# design.net
KiCad netlist of a schematic drawn in EasyEDA
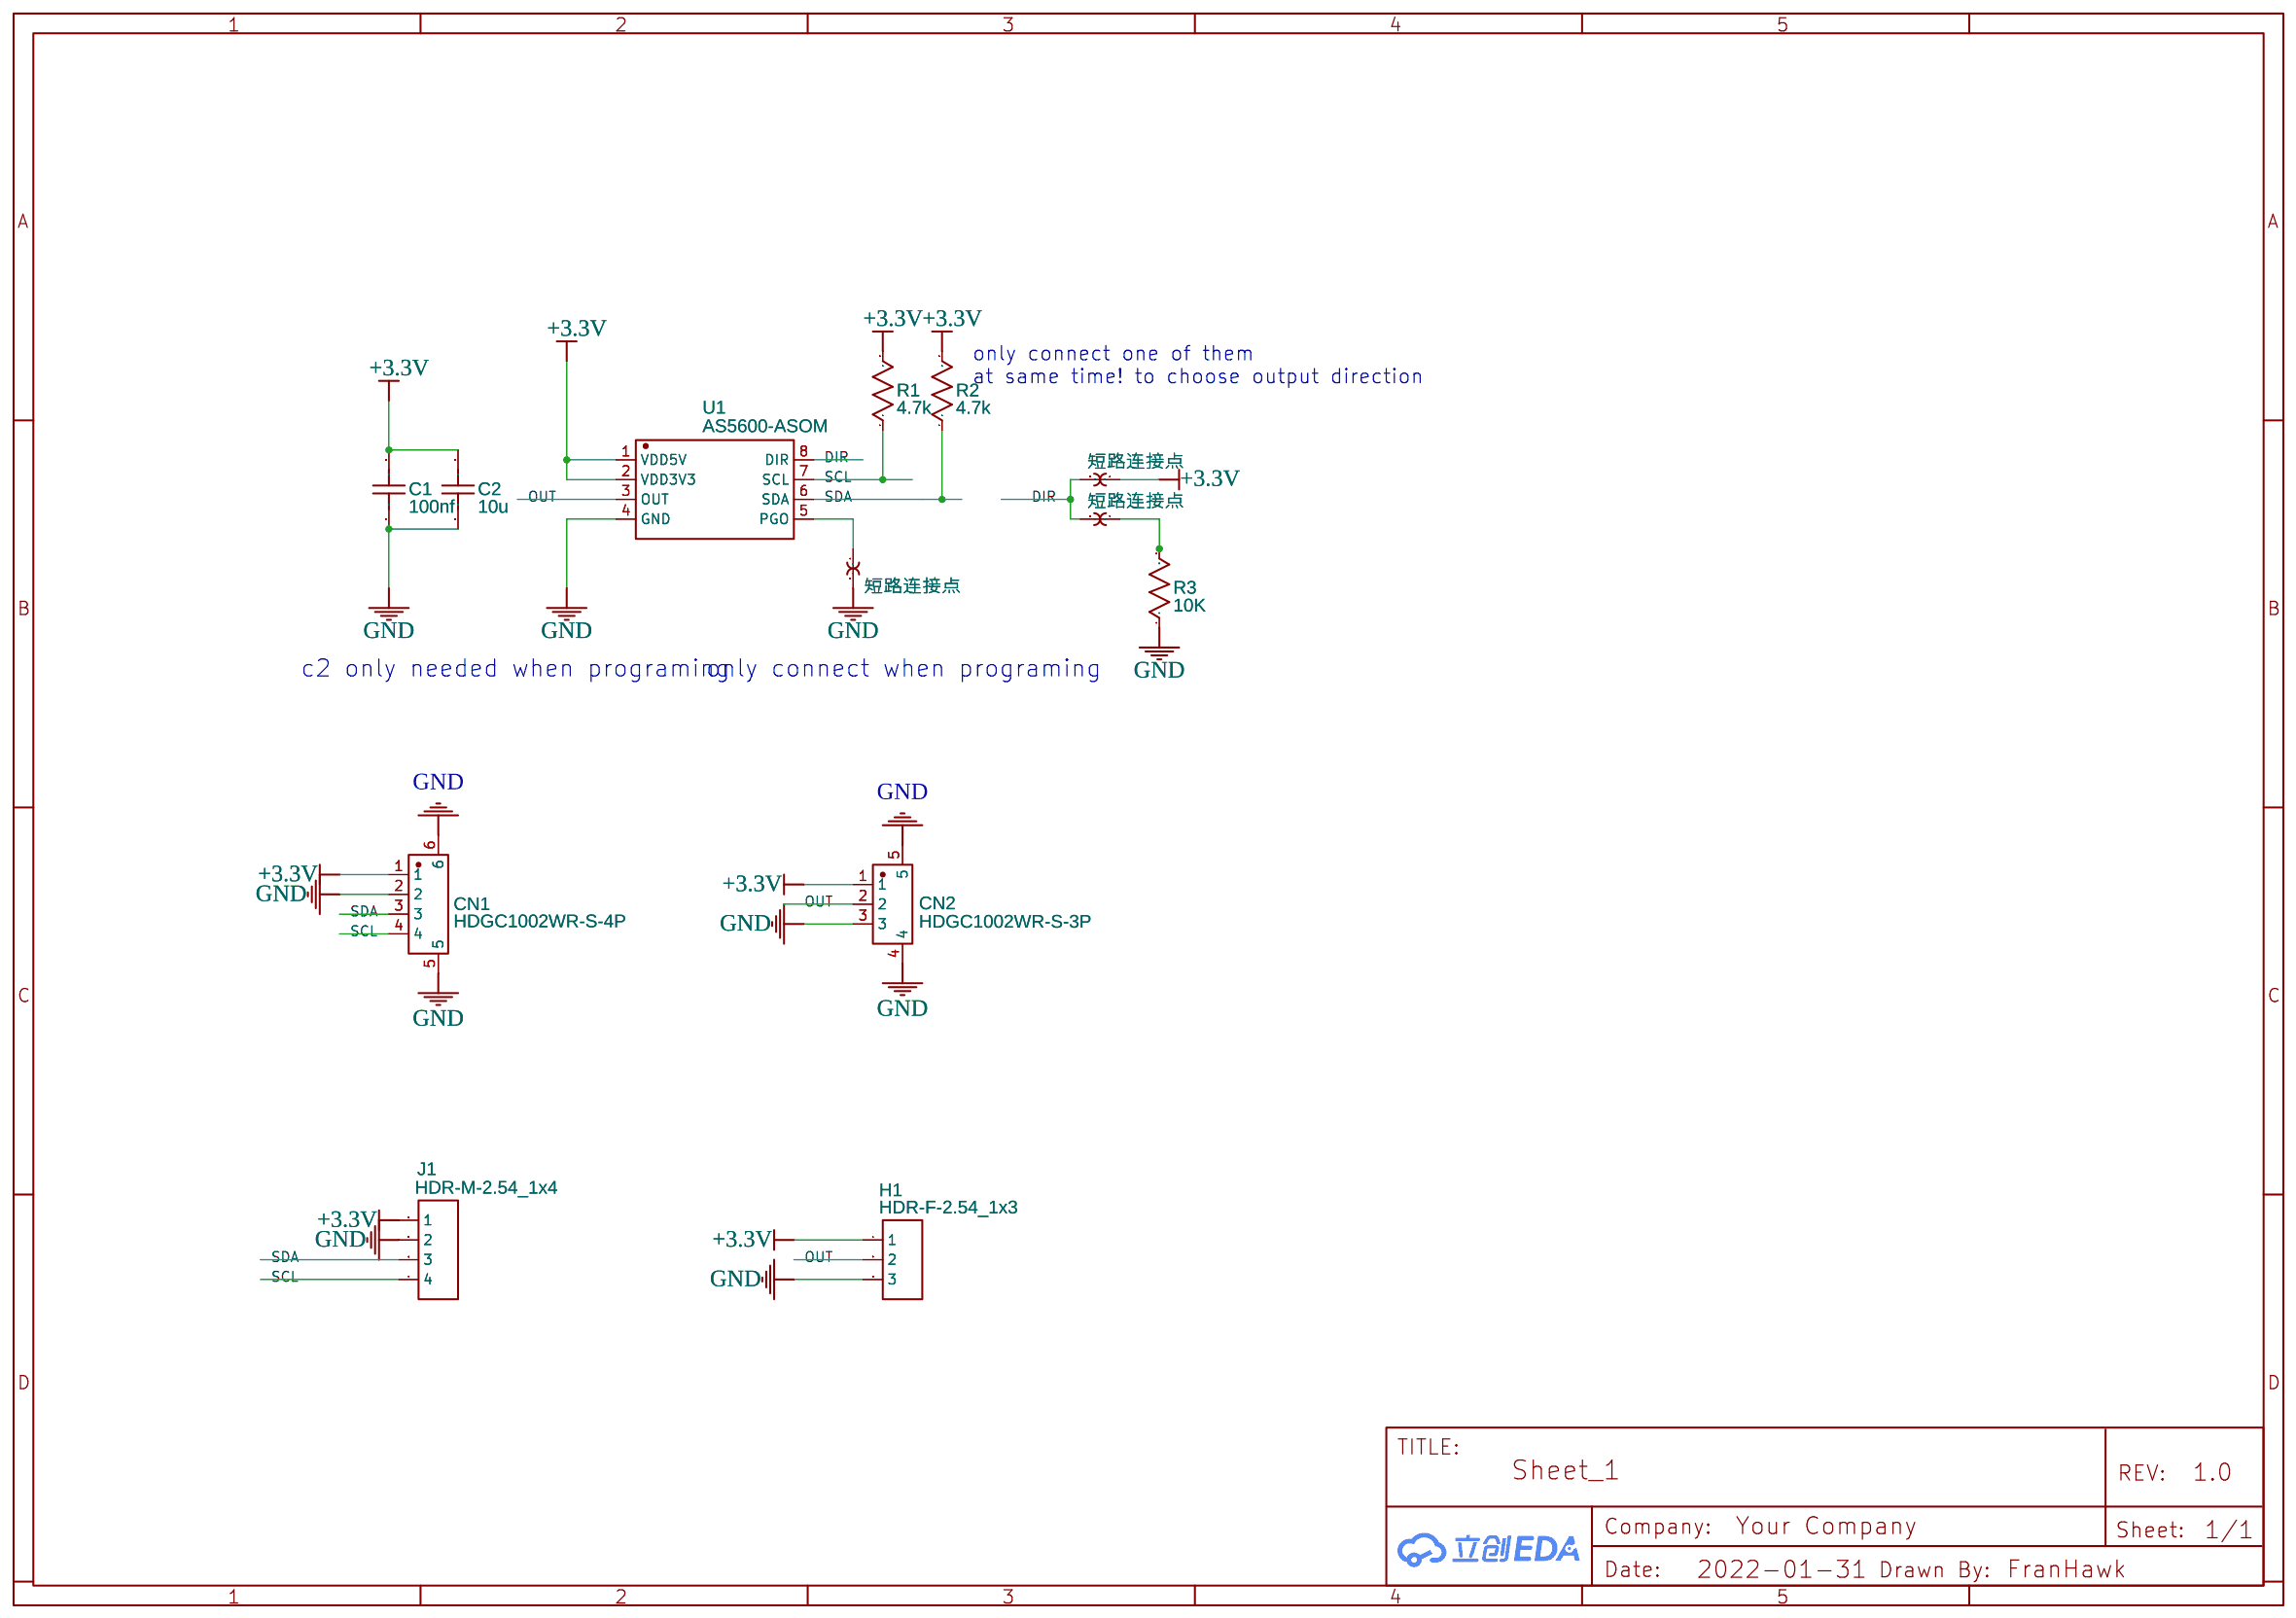
[diagram p0: schematic sheet]

(export (version "E")
  (design (tool "Eeschema 10.0.6"))
  (components
    (comp (ref "C1") (value "100nf") (libsource (lib "") (part "C_0603_US")))
    (comp (ref "C2") (value "10u") (libsource (lib "") (part "C_0603_US")))
    (comp (ref "CN1")
      (value "HDGC1002WR-S-4P")
      (fields (field (name "BOM_Supplier Part") "C2936214"))
      (libsource (lib "") (part "HDGC1002WR-S-4P"))
    )
    (comp (ref "CN2")
      (value "HDGC1002WR-S-3P")
      (fields (field (name "BOM_Supplier Part") "C2936213"))
      (libsource (lib "") (part "HDGC1002WR-S-3P"))
    )
    (comp (ref "H1")
      (value "HDR-F-2.54_1x3")
      (fields (field (name "BOM_Supplier Part") "C146690"))
      (libsource (lib "") (part "HDR-F-2.54_1x3"))
    )
    (comp (ref "J1")
      (value "HDR-M-2.54_1x4")
      (fields (field (name "BOM_Supplier Part") "C124378"))
      (libsource (lib "") (part "HDR-M-2.54_1x4"))
    )
    (comp (ref "NO1") (value "短路连接点") (libsource (lib "") (part "短路连接点_1")))
    (comp (ref "NO2") (value "短路连接点") (libsource (lib "") (part "短路连接点")))
    (comp (ref "NO3") (value "短路连接点") (libsource (lib "") (part "短路连接点")))
    (comp (ref "R1") (value "4.7k") (libsource (lib "") (part "R_0603_US")))
    (comp (ref "R2") (value "4.7k") (libsource (lib "") (part "R_0603_US")))
    (comp (ref "R3") (value "10K") (libsource (lib "") (part "R_0603_US")))
    (comp (ref "U1")
      (value "AS5600-ASOM")
      (fields (field (name "BOM_Supplier Part") "C79815"))
      (libsource (lib "") (part "AS5600-ASOM"))
    )
  )
  (nets
    (net (code "1") (name "+3.3V") (class "Default")
      (node (ref "C1") (pin "2") (pinfunction "2_2") (pintype "unspecified"))
      (node (ref "C2") (pin "2") (pinfunction "2_2") (pintype "unspecified"))
      (node (ref "CN1") (pin "1") (pinfunction "1_1") (pintype "unspecified"))
      (node (ref "CN2") (pin "1") (pinfunction "1_1") (pintype "unspecified"))
      (node (ref "H1") (pin "1") (pinfunction "1_1") (pintype "input"))
      (node (ref "J1") (pin "1") (pinfunction "1_1") (pintype "unspecified"))
      (node (ref "NO3") (pin "1") (pinfunction "1_1") (pintype "unspecified"))
      (node (ref "R1") (pin "2") (pinfunction "2_2") (pintype "unspecified"))
      (node (ref "R2") (pin "2") (pinfunction "2_2") (pintype "unspecified"))
      (node (ref "U1") (pin "1") (pinfunction "VDD5V_1") (pintype "unspecified"))
      (node (ref "U1") (pin "2") (pinfunction "VDD3V3_2") (pintype "unspecified"))
    )
    (net (code "2") (name "/DIR") (class "Default")
      (node (ref "NO2") (pin "2") (pinfunction "2_2") (pintype "unspecified"))
      (node (ref "NO3") (pin "2") (pinfunction "2_2") (pintype "unspecified"))
      (node (ref "U1") (pin "8") (pinfunction "DIR_8") (pintype "unspecified"))
    )
    (net (code "3") (name "/OUT") (class "Default")
      (node (ref "CN2") (pin "2") (pinfunction "2_2") (pintype "unspecified"))
      (node (ref "H1") (pin "2") (pinfunction "2_2") (pintype "input"))
      (node (ref "U1") (pin "3") (pinfunction "OUT_3") (pintype "unspecified"))
    )
    (net (code "4") (name "/SCL") (class "Default")
      (node (ref "CN1") (pin "4") (pinfunction "4_4") (pintype "unspecified"))
      (node (ref "J1") (pin "4") (pinfunction "4_4") (pintype "unspecified"))
      (node (ref "R1") (pin "1") (pinfunction "1_1") (pintype "unspecified"))
      (node (ref "U1") (pin "7") (pinfunction "SCL_7") (pintype "unspecified"))
    )
    (net (code "5") (name "/SDA") (class "Default")
      (node (ref "CN1") (pin "3") (pinfunction "3_3") (pintype "unspecified"))
      (node (ref "J1") (pin "3") (pinfunction "3_3") (pintype "unspecified"))
      (node (ref "R2") (pin "1") (pinfunction "1_1") (pintype "unspecified"))
      (node (ref "U1") (pin "6") (pinfunction "SDA_6") (pintype "unspecified"))
    )
    (net (code "6") (name "GND") (class "Default")
      (node (ref "C1") (pin "1") (pinfunction "1_1") (pintype "unspecified"))
      (node (ref "C2") (pin "1") (pinfunction "1_1") (pintype "unspecified"))
      (node (ref "CN1") (pin "2") (pinfunction "2_2") (pintype "unspecified"))
      (node (ref "CN1") (pin "5") (pinfunction "5_5") (pintype "unspecified"))
      (node (ref "CN1") (pin "6") (pinfunction "6_6") (pintype "unspecified"))
      (node (ref "CN2") (pin "3") (pinfunction "3_3") (pintype "unspecified"))
      (node (ref "CN2") (pin "4") (pinfunction "4_4") (pintype "unspecified"))
      (node (ref "CN2") (pin "5") (pinfunction "5_5") (pintype "unspecified"))
      (node (ref "H1") (pin "3") (pinfunction "3_3") (pintype "input"))
      (node (ref "J1") (pin "2") (pinfunction "2_2") (pintype "unspecified"))
      (node (ref "NO1") (pin "2") (pinfunction "2_2") (pintype "unspecified"))
      (node (ref "R3") (pin "1") (pinfunction "1_1") (pintype "unspecified"))
      (node (ref "U1") (pin "4") (pinfunction "GND_4") (pintype "unspecified"))
    )
    (net (code "7") (name "Net-(NO2-Pad1)") (class "Default")
      (node (ref "NO2") (pin "1") (pinfunction "1_1") (pintype "unspecified"))
      (node (ref "R3") (pin "2") (pinfunction "2_2") (pintype "unspecified"))
    )
    (net (code "8") (name "Net-(U1-PGO)") (class "Default")
      (node (ref "NO1") (pin "1") (pinfunction "1_1") (pintype "unspecified"))
      (node (ref "U1") (pin "5") (pinfunction "PGO_5") (pintype "unspecified"))
    )
  )
)
